# Power.net
KiCad netlist of a schematic drawn in Altium Designer
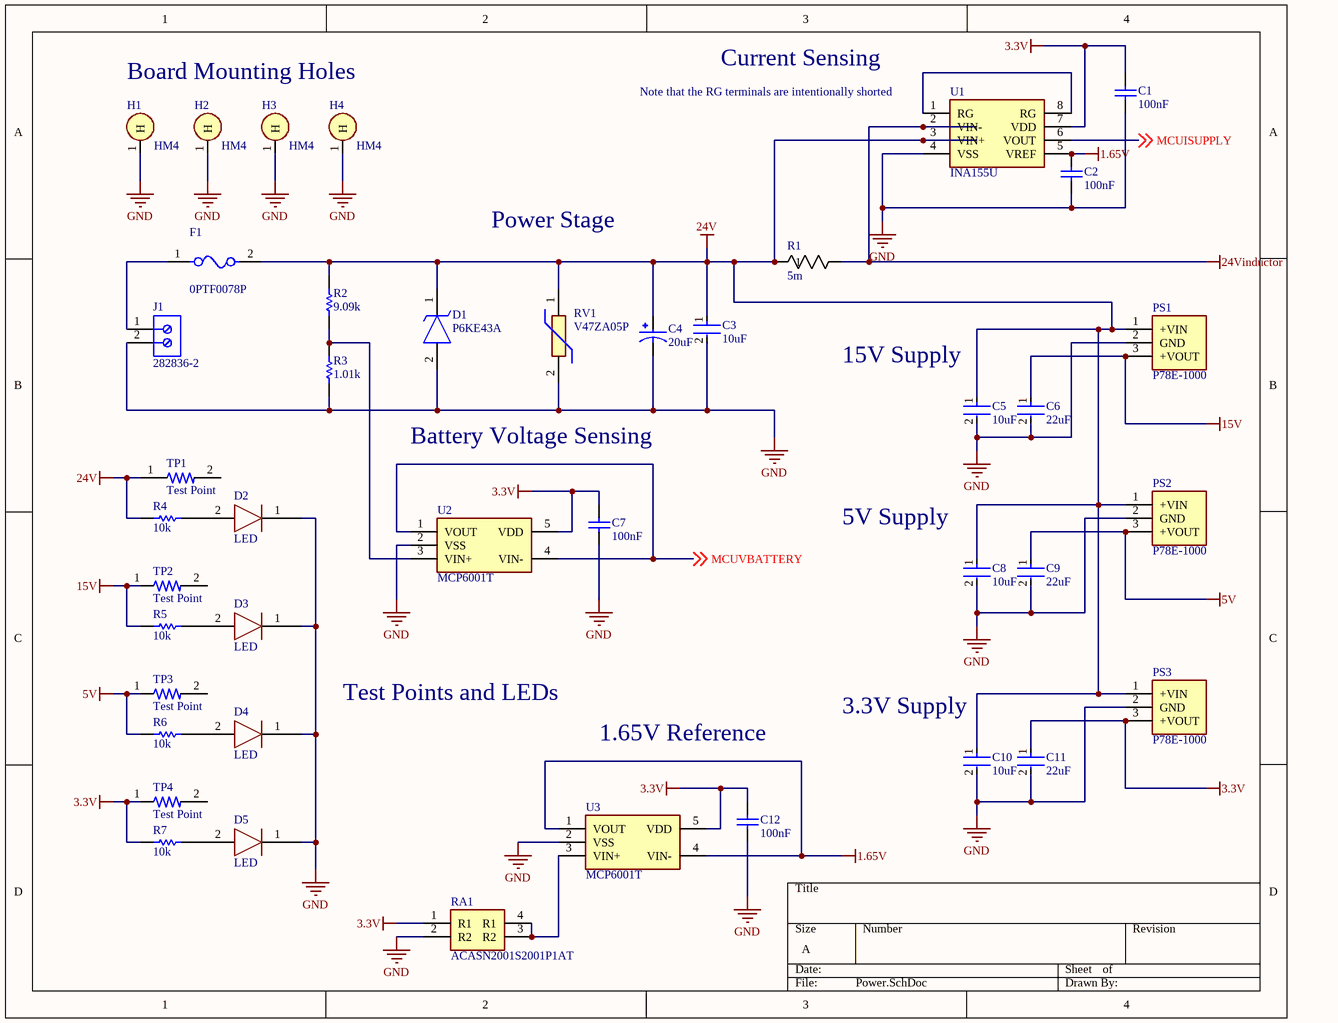
[diagram p0: Power.SchDoc]

(export (version "E")
  (design (tool "Eeschema 10.0.6"))
  (components
    (comp (ref "C1")
      (value "100nF")
      (footprint "CAPC1609X100X15LL20")
      (fields
        (field (name "MANUFACTURER") "AVX Interconnect / Elco")
        (field (name "PART NUMBER") "TACL105M006XTA")
      )
      (libsource (lib "Altium Content Vault") (part "CAP"))
    )
    (comp (ref "C2")
      (value "100nF")
      (footprint "CAPC1609X100X15LL20")
      (fields
        (field (name "MANUFACTURER") "AVX Interconnect / Elco")
        (field (name "PART NUMBER") "TACL105M006XTA")
      )
      (libsource (lib "Altium Content Vault") (part "CAP"))
    )
    (comp (ref "C3")
      (value "10uF")
      (footprint "FP-CL31-IPC_C")
      (description "Cap Ceramic 220pF 500V C0G ±5% SMD 1206 +125°C Embossed T/R CL31C221JGFNNNF")
      (fields (field (name "TOLERANCE") "5%"))
      (libsource (lib "Altium Content Vault") (part "b4654b650e69147ec39a6b967a45e02"))
    )
    (comp (ref "C4")
      (value "20uF")
      (footprint "CAP_EEEFK1V180SR")
      (description "CAP ALUM 18UF 20% 35V SMD")
      (fields (field (name "MP") "EEEFK1V180SR") (field (name "DIGI-KEY_PART_NUMBER") "PCE5153TR-ND"))
      (libsource (lib "EEEFK1V180SR") (part "EEEFK1V180SR"))
    )
    (comp (ref "C5")
      (value "10uF")
      (footprint "FP-CL31-IPC_C")
      (description "Cap Ceramic 220pF 500V C0G ±5% SMD 1206 +125°C Embossed T/R CL31C221JGFNNNF")
      (fields (field (name "TOLERANCE") "5%"))
      (libsource (lib "Altium Content Vault") (part "b4654b650e69147ec39a6b967a45e02"))
    )
    (comp (ref "C6")
      (value "22uF")
      (footprint "FP-RDEWK1-MFG")
      (description "CAP CER 22UF 50V X7S RADIAL RDEC71H226MWK1H03B")
      (fields (field (name "TOLERANCE") "20%"))
      (libsource (lib "Altium Content Vault") (part "02cd4be3c70576c341d710602a673aa"))
    )
    (comp (ref "C7")
      (value "100nF")
      (footprint "CAPC1609X100X15LL20")
      (fields
        (field (name "MANUFACTURER") "AVX Interconnect / Elco")
        (field (name "PART NUMBER") "TACL105M006XTA")
      )
      (libsource (lib "Altium Content Vault") (part "CAP"))
    )
    (comp (ref "C8")
      (value "10uF")
      (footprint "FP-CL31-IPC_C")
      (description "Cap Ceramic 220pF 500V C0G ±5% SMD 1206 +125°C Embossed T/R CL31C221JGFNNNF")
      (fields (field (name "TOLERANCE") "5%"))
      (libsource (lib "Altium Content Vault") (part "b4654b650e69147ec39a6b967a45e02"))
    )
    (comp (ref "C9")
      (value "22uF")
      (footprint "FP-RDEWK1-MFG")
      (description "CAP CER 22UF 50V X7S RADIAL RDEC71H226MWK1H03B")
      (fields (field (name "TOLERANCE") "20%"))
      (libsource (lib "Altium Content Vault") (part "02cd4be3c70576c341d710602a673aa"))
    )
    (comp (ref "C10")
      (value "10uF")
      (footprint "FP-CL31-IPC_C")
      (description "Cap Ceramic 220pF 500V C0G ±5% SMD 1206 +125°C Embossed T/R CL31C221JGFNNNF")
      (fields (field (name "TOLERANCE") "5%"))
      (libsource (lib "Altium Content Vault") (part "b4654b650e69147ec39a6b967a45e02"))
    )
    (comp (ref "C11")
      (value "22uF")
      (footprint "FP-RDEWK1-MFG")
      (description "CAP CER 22UF 50V X7S RADIAL RDEC71H226MWK1H03B")
      (fields (field (name "TOLERANCE") "20%"))
      (libsource (lib "Altium Content Vault") (part "02cd4be3c70576c341d710602a673aa"))
    )
    (comp (ref "C12")
      (value "100nF")
      (footprint "CAPC1609X100X15LL20")
      (fields
        (field (name "MANUFACTURER") "AVX Interconnect / Elco")
        (field (name "PART NUMBER") "TACL105M006XTA")
      )
      (libsource (lib "Altium Content Vault") (part "CAP"))
    )
    (comp (ref "D1")
      (value "P6KE43A")
      (footprint "SamacSys:DIOAD1910W86L670D310")
      (description "TVS Diode (Uni-directional)")
      (fields (field (name "MANUFACTURER_PART_NUMBER") "P6KE91A-E3/54"))
      (libsource (lib "*") (part "P6KE91A-E3_54"))
    )
    (comp (ref "D2")
      (value "LED")
      (footprint "LED 0603")
      (description "LED SMD")
      (libsource (lib "ee_453_yourname") (part "LED"))
    )
    (comp (ref "D3")
      (value "LED")
      (footprint "LED 0603")
      (description "LED SMD")
      (libsource (lib "ee_453_yourname") (part "LED"))
    )
    (comp (ref "D4")
      (value "LED")
      (footprint "LED 0603")
      (description "LED SMD")
      (libsource (lib "ee_453_yourname") (part "LED"))
    )
    (comp (ref "D5")
      (value "LED")
      (footprint "LED 0603")
      (description "LED SMD")
      (libsource (lib "ee_453_yourname") (part "LED"))
    )
    (comp (ref "F1")
      (value "0PTF0078P")
      (footprint "FP-0PTF0078P-MFG")
      (description "FUSE BLOCK CARTRIDGE PCB")
      (fields
        (field (name "OCTOPART") "https://octopart.com/0ptf0078p-littelfuse-13255855")
        (field (name "MANUFACTURER") "Littelfuse Inc")
      )
      (libsource (lib "Altium Content Vault") (part "5bcf9b9f640e542cf0359d10258e979"))
    )
    (comp (ref "H1")
      (value "HM4")
      (footprint "M4 Hole")
      (description "M$ Mounting Hole")
      (libsource (lib "ee_453_yourname") (part "HM4"))
    )
    (comp (ref "H2")
      (value "HM4")
      (footprint "M4 Hole")
      (description "M$ Mounting Hole")
      (libsource (lib "ee_453_yourname") (part "HM4"))
    )
    (comp (ref "H3")
      (value "HM4")
      (footprint "M4 Hole")
      (description "M$ Mounting Hole")
      (libsource (lib "ee_453_yourname") (part "HM4"))
    )
    (comp (ref "H4")
      (value "HM4")
      (footprint "M4 Hole")
      (description "M$ Mounting Hole")
      (libsource (lib "ee_453_yourname") (part "HM4"))
    )
    (comp (ref "J1")
      (value "282836-2")
      (footprint "TECO-282836-2_V")
      (description "Female Header, Pitch 5 mm, 1 x 2 Position, Height 10 mm, Tail Length 3.5 mm, Rohs, Bulk")
      (fields (field (name "VOLTAGE") "300V") (field (name "MANUFACTURER") "TE Connectivity"))
      (libsource (lib "Altium Content Vault") (part "CN-1P-F-TB2"))
    )
    (comp (ref "PS1")
      (value "P78E-1000")
      (footprint "P78E-1000")
      (description "DC-DC Converter")
      (libsource (lib "ee_453_yourname") (part "P78E-1000"))
    )
    (comp (ref "PS2")
      (value "P78E-1000")
      (footprint "P78E-1000")
      (description "DC-DC Converter")
      (libsource (lib "ee_453_yourname") (part "P78E-1000"))
    )
    (comp (ref "PS3")
      (value "P78E-1000")
      (footprint "P78E-1000")
      (description "DC-DC Converter")
      (libsource (lib "ee_453_yourname") (part "P78E-1000"))
    )
    (comp (ref "R1")
      (value "5m")
      (footprint "RES_BR3_STP")
      (description "No Description Available")
      (fields
        (field (name "MANUFACTURER_PART_NUMBER") "BR3FB5L00")
        (field (name "COPYRIGHT") "Copyright (C) 2022 Ultra Librarian. All rights reserved.")
      )
      (libsource (lib "BR3FB5L00") (part "BR3FB5L00"))
    )
    (comp (ref "R2")
      (value "9.09k")
      (footprint "RESC1609X50X30NL8T20")
      (description "Chip Resistor, 0 Ohm, Jumper, 100 mW, -55 to 155 degC, 0603 (1608 Metric), RoHS, Tape and Reel")
      (fields (field (name "MANUFACTURER") "Vishay Semiconductor"))
      (libsource (lib "Altium Content Vault") (part "RES-2"))
    )
    (comp (ref "R3")
      (value "1.01k")
      (footprint "RESC1609X50X30NL8T20")
      (description "Chip Resistor, 0 Ohm, Jumper, 100 mW, -55 to 155 degC, 0603 (1608 Metric), RoHS, Tape and Reel")
      (fields (field (name "MANUFACTURER") "Vishay Semiconductor"))
      (libsource (lib "Altium Content Vault") (part "RES-2"))
    )
    (comp (ref "R4")
      (value "10k")
      (footprint "RESC1609X50X30NL8T20")
      (description "Chip Resistor, 0 Ohm, Jumper, 100 mW, -55 to 155 degC, 0603 (1608 Metric), RoHS, Tape and Reel")
      (fields (field (name "MANUFACTURER") "Vishay Semiconductor"))
      (libsource (lib "Altium Content Vault") (part "RES-2"))
    )
    (comp (ref "R5")
      (value "10k")
      (footprint "RESC1609X50X30NL8T20")
      (description "Chip Resistor, 0 Ohm, Jumper, 100 mW, -55 to 155 degC, 0603 (1608 Metric), RoHS, Tape and Reel")
      (fields (field (name "MANUFACTURER") "Vishay Semiconductor"))
      (libsource (lib "Altium Content Vault") (part "RES-2"))
    )
    (comp (ref "R6")
      (value "10k")
      (footprint "RESC1609X50X30NL8T20")
      (description "Chip Resistor, 0 Ohm, Jumper, 100 mW, -55 to 155 degC, 0603 (1608 Metric), RoHS, Tape and Reel")
      (fields (field (name "MANUFACTURER") "Vishay Semiconductor"))
      (libsource (lib "Altium Content Vault") (part "RES-2"))
    )
    (comp (ref "R7")
      (value "10k")
      (footprint "RESC1609X50X30NL8T20")
      (description "Chip Resistor, 0 Ohm, Jumper, 100 mW, -55 to 155 degC, 0603 (1608 Metric), RoHS, Tape and Reel")
      (fields (field (name "MANUFACTURER") "Vishay Semiconductor"))
      (libsource (lib "Altium Content Vault") (part "RES-2"))
    )
    (comp (ref "RA1")
      (value "ACASN2001S2001P1AT")
      (footprint "0606")
      (description "Matched Resistor Array")
      (libsource (lib "ee_453_yourname") (part "ACASN2001S2001P1AT"))
    )
    (comp (ref "RV1")
      (value "V47ZA05P")
      (footprint "SamacSys:V68ZS10P")
      (description "Varistor")
      (fields
        (field (name "MANUFACTURER_PART_NUMBER") "V68ZS10P")
        (field (name "MOUSER PART NUMBER") "576-V68ZS10P")
      )
      (libsource (lib "*") (part "V68ZS10P"))
    )
    (comp (ref "TP1")
      (value "Test Point")
      (footprint "RESC3216X70N")
      (description "PC Test Point , Plating Surface Mount Mounting Type")
      (fields (field (name "MF") "KOA Speer") (field (name "MP") "RCWCTE"))
      (libsource (lib "SnapEDAsch") (part "RCWCTE"))
    )
    (comp (ref "TP2")
      (value "Test Point")
      (footprint "RESC3216X70N")
      (description "PC Test Point , Plating Surface Mount Mounting Type")
      (fields (field (name "MF") "KOA Speer") (field (name "MP") "RCWCTE"))
      (libsource (lib "SnapEDAsch") (part "RCWCTE"))
    )
    (comp (ref "TP3")
      (value "Test Point")
      (footprint "RESC3216X70N")
      (description "PC Test Point , Plating Surface Mount Mounting Type")
      (fields (field (name "MF") "KOA Speer") (field (name "MP") "RCWCTE"))
      (libsource (lib "SnapEDAsch") (part "RCWCTE"))
    )
    (comp (ref "TP4")
      (value "Test Point")
      (footprint "RESC3216X70N")
      (description "PC Test Point , Plating Surface Mount Mounting Type")
      (fields (field (name "MF") "KOA Speer") (field (name "MP") "RCWCTE"))
      (libsource (lib "SnapEDAsch") (part "RCWCTE"))
    )
    (comp (ref "U1")
      (value "INA155U")
      (footprint "SOIC8")
      (description "In-Amp")
      (libsource (lib "ee_453_yourname") (part "INA155U"))
    )
    (comp (ref "U2")
      (value "MCP6001T")
      (footprint "SOT-23")
      (description "Op-Amp")
      (libsource (lib "ee_453_yourname") (part "MCP6001T"))
    )
    (comp (ref "U3")
      (value "MCP6001T")
      (footprint "SOT-23")
      (description "Op-Amp")
      (libsource (lib "ee_453_yourname") (part "MCP6001T"))
    )
  )
  (nets
    (net (code "1") (name "1.65V") (class "Default")
      (node (ref "C2") (pin "2") (pinfunction "2_2") (pintype "passive"))
      (node (ref "U1") (pin "5") (pinfunction "VREF_5") (pintype "passive"))
      (node (ref "U3") (pin "1") (pinfunction "VOUT_1") (pintype "passive"))
      (node (ref "U3") (pin "4") (pinfunction "VIN-_4") (pintype "passive"))
    )
    (net (code "2") (name "3.3V") (class "Default")
      (node (ref "C1") (pin "2") (pinfunction "2_2") (pintype "passive"))
      (node (ref "C11") (pin "1") (pinfunction "1_1") (pintype "passive"))
      (node (ref "C12") (pin "2") (pinfunction "2_2") (pintype "passive"))
      (node (ref "C7") (pin "2") (pinfunction "2_2") (pintype "passive"))
      (node (ref "PS3") (pin "3") (pinfunction "+VOUT_3") (pintype "passive"))
      (node (ref "R7") (pin "1") (pinfunction "1_1") (pintype "passive"))
      (node (ref "RA1") (pin "1") (pinfunction "R1_1") (pintype "passive"))
      (node (ref "TP4") (pin "1") (pinfunction "1_1") (pintype "passive"))
      (node (ref "U1") (pin "7") (pinfunction "VDD_7") (pintype "passive"))
      (node (ref "U2") (pin "5") (pinfunction "VDD_5") (pintype "passive"))
      (node (ref "U3") (pin "5") (pinfunction "VDD_5") (pintype "passive"))
    )
    (net (code "3") (name "5V") (class "Default")
      (node (ref "C9") (pin "1") (pinfunction "1_1") (pintype "passive"))
      (node (ref "PS2") (pin "3") (pinfunction "+VOUT_3") (pintype "passive"))
      (node (ref "R6") (pin "1") (pinfunction "1_1") (pintype "passive"))
      (node (ref "TP3") (pin "1") (pinfunction "1_1") (pintype "passive"))
    )
    (net (code "4") (name "15V") (class "Default")
      (node (ref "C6") (pin "1") (pinfunction "1_1") (pintype "passive"))
      (node (ref "PS1") (pin "3") (pinfunction "+VOUT_3") (pintype "passive"))
      (node (ref "R5") (pin "1") (pinfunction "1_1") (pintype "passive"))
      (node (ref "TP2") (pin "1") (pinfunction "1_1") (pintype "passive"))
    )
    (net (code "5") (name "24V") (class "Default")
      (node (ref "C10") (pin "1") (pinfunction "1_1") (pintype "passive"))
      (node (ref "C3") (pin "1") (pinfunction "1_1") (pintype "passive"))
      (node (ref "C4") (pin "1") (pinfunction "1_1") (pintype "passive"))
      (node (ref "C5") (pin "1") (pinfunction "1_1") (pintype "passive"))
      (node (ref "C8") (pin "1") (pinfunction "1_1") (pintype "passive"))
      (node (ref "D1") (pin "1") (pinfunction "K_1") (pintype "passive"))
      (node (ref "F1") (pin "2") (pinfunction "2_2") (pintype "passive"))
      (node (ref "PS1") (pin "1") (pinfunction "+VIN_1") (pintype "passive"))
      (node (ref "PS2") (pin "1") (pinfunction "+VIN_1") (pintype "passive"))
      (node (ref "PS3") (pin "1") (pinfunction "+VIN_1") (pintype "passive"))
      (node (ref "R1") (pin "1") (pinfunction "1_1") (pintype "passive"))
      (node (ref "R2") (pin "2") (pinfunction "2_2") (pintype "passive"))
      (node (ref "R4") (pin "1") (pinfunction "1_1") (pintype "passive"))
      (node (ref "RV1") (pin "1") (pinfunction "1_1") (pintype "passive"))
      (node (ref "TP1") (pin "1") (pinfunction "1_1") (pintype "passive"))
      (node (ref "U1") (pin "3") (pinfunction "VIN+_3") (pintype "passive"))
    )
    (net (code "6") (name "24Vinductor") (class "Default")
      (node (ref "R1") (pin "2") (pinfunction "2_2") (pintype "passive"))
      (node (ref "U1") (pin "2") (pinfunction "VIN-_2") (pintype "passive"))
    )
    (net (code "7") (name "GND") (class "Default")
      (node (ref "C1") (pin "1") (pinfunction "1_1") (pintype "passive"))
      (node (ref "C10") (pin "2") (pinfunction "2_2") (pintype "passive"))
      (node (ref "C11") (pin "2") (pinfunction "2_2") (pintype "passive"))
      (node (ref "C12") (pin "1") (pinfunction "1_1") (pintype "passive"))
      (node (ref "C2") (pin "1") (pinfunction "1_1") (pintype "passive"))
      (node (ref "C3") (pin "2") (pinfunction "2_2") (pintype "passive"))
      (node (ref "C4") (pin "2") (pinfunction "2_2") (pintype "passive"))
      (node (ref "C5") (pin "2") (pinfunction "2_2") (pintype "passive"))
      (node (ref "C6") (pin "2") (pinfunction "2_2") (pintype "passive"))
      (node (ref "C7") (pin "1") (pinfunction "1_1") (pintype "passive"))
      (node (ref "C8") (pin "2") (pinfunction "2_2") (pintype "passive"))
      (node (ref "C9") (pin "2") (pinfunction "2_2") (pintype "passive"))
      (node (ref "D1") (pin "2") (pinfunction "A_2") (pintype "passive"))
      (node (ref "D2") (pin "1") (pintype "passive"))
      (node (ref "D3") (pin "1") (pintype "passive"))
      (node (ref "D4") (pin "1") (pintype "passive"))
      (node (ref "D5") (pin "1") (pintype "passive"))
      (node (ref "H1") (pin "1") (pinfunction "H_1") (pintype "passive"))
      (node (ref "H2") (pin "1") (pinfunction "H_1") (pintype "passive"))
      (node (ref "H3") (pin "1") (pinfunction "H_1") (pintype "passive"))
      (node (ref "H4") (pin "1") (pinfunction "H_1") (pintype "passive"))
      (node (ref "J1") (pin "2") (pinfunction "2_2") (pintype "passive"))
      (node (ref "PS1") (pin "2") (pinfunction "GND_2") (pintype "passive"))
      (node (ref "PS2") (pin "2") (pinfunction "GND_2") (pintype "passive"))
      (node (ref "PS3") (pin "2") (pinfunction "GND_2") (pintype "passive"))
      (node (ref "R3") (pin "1") (pinfunction "1_1") (pintype "passive"))
      (node (ref "RA1") (pin "2") (pinfunction "R2_2") (pintype "passive"))
      (node (ref "RV1") (pin "2") (pinfunction "2_2") (pintype "passive"))
      (node (ref "U1") (pin "4") (pinfunction "VSS_4") (pintype "passive"))
      (node (ref "U2") (pin "2") (pinfunction "VSS_2") (pintype "passive"))
      (node (ref "U3") (pin "2") (pinfunction "VSS_2") (pintype "passive"))
    )
    (net (code "8") (name "MCUISUPPLY") (class "Default")
      (node (ref "U1") (pin "6") (pinfunction "VOUT_6") (pintype "passive"))
    )
    (net (code "9") (name "MCUVBATTERY") (class "Default")
      (node (ref "U2") (pin "1") (pinfunction "VOUT_1") (pintype "passive"))
      (node (ref "U2") (pin "4") (pinfunction "VIN-_4") (pintype "passive"))
    )
    (net (code "10") (name "Net-(D2-Pad2)") (class "Default")
      (node (ref "D2") (pin "2") (pintype "passive"))
      (node (ref "R4") (pin "2") (pinfunction "2_2") (pintype "passive"))
    )
    (net (code "11") (name "Net-(D3-Pad2)") (class "Default")
      (node (ref "D3") (pin "2") (pintype "passive"))
      (node (ref "R5") (pin "2") (pinfunction "2_2") (pintype "passive"))
    )
    (net (code "12") (name "Net-(D4-Pad2)") (class "Default")
      (node (ref "D4") (pin "2") (pintype "passive"))
      (node (ref "R6") (pin "2") (pinfunction "2_2") (pintype "passive"))
    )
    (net (code "13") (name "Net-(D5-Pad2)") (class "Default")
      (node (ref "D5") (pin "2") (pintype "passive"))
      (node (ref "R7") (pin "2") (pinfunction "2_2") (pintype "passive"))
    )
    (net (code "14") (name "Net-(F1-Pad1)") (class "Default")
      (node (ref "F1") (pin "1") (pinfunction "1_1") (pintype "passive"))
      (node (ref "J1") (pin "1") (pinfunction "1_1") (pintype "passive"))
    )
    (net (code "15") (name "Net-(U1-RG-Pad1)") (class "Default")
      (node (ref "U1") (pin "1") (pinfunction "RG_1") (pintype "passive"))
      (node (ref "U1") (pin "8") (pinfunction "RG_8") (pintype "passive"))
    )
    (net (code "16") (name "Net-(U2-VIN+)") (class "Default")
      (node (ref "R2") (pin "1") (pinfunction "1_1") (pintype "passive"))
      (node (ref "R3") (pin "2") (pinfunction "2_2") (pintype "passive"))
      (node (ref "U2") (pin "3") (pinfunction "VIN+_3") (pintype "passive"))
    )
    (net (code "17") (name "Net-(U3-VIN+)") (class "Default")
      (node (ref "RA1") (pin "3") (pinfunction "R2_3") (pintype "passive"))
      (node (ref "RA1") (pin "4") (pinfunction "R1_4") (pintype "passive"))
      (node (ref "U3") (pin "3") (pinfunction "VIN+_3") (pintype "passive"))
    )
    (net (code "18") (name "unconnected-(TP1-Pad2)") (class "Default")
      (node (ref "TP1") (pin "2") (pinfunction "2_2") (pintype "passive"))
    )
    (net (code "19") (name "unconnected-(TP2-Pad2)") (class "Default")
      (node (ref "TP2") (pin "2") (pinfunction "2_2") (pintype "passive"))
    )
    (net (code "20") (name "unconnected-(TP3-Pad2)") (class "Default")
      (node (ref "TP3") (pin "2") (pinfunction "2_2") (pintype "passive"))
    )
    (net (code "21") (name "unconnected-(TP4-Pad2)") (class "Default")
      (node (ref "TP4") (pin "2") (pinfunction "2_2") (pintype "passive"))
    )
  )
)
